# Reference_2V5.net
KiCad netlist of a schematic drawn in Altium Designer
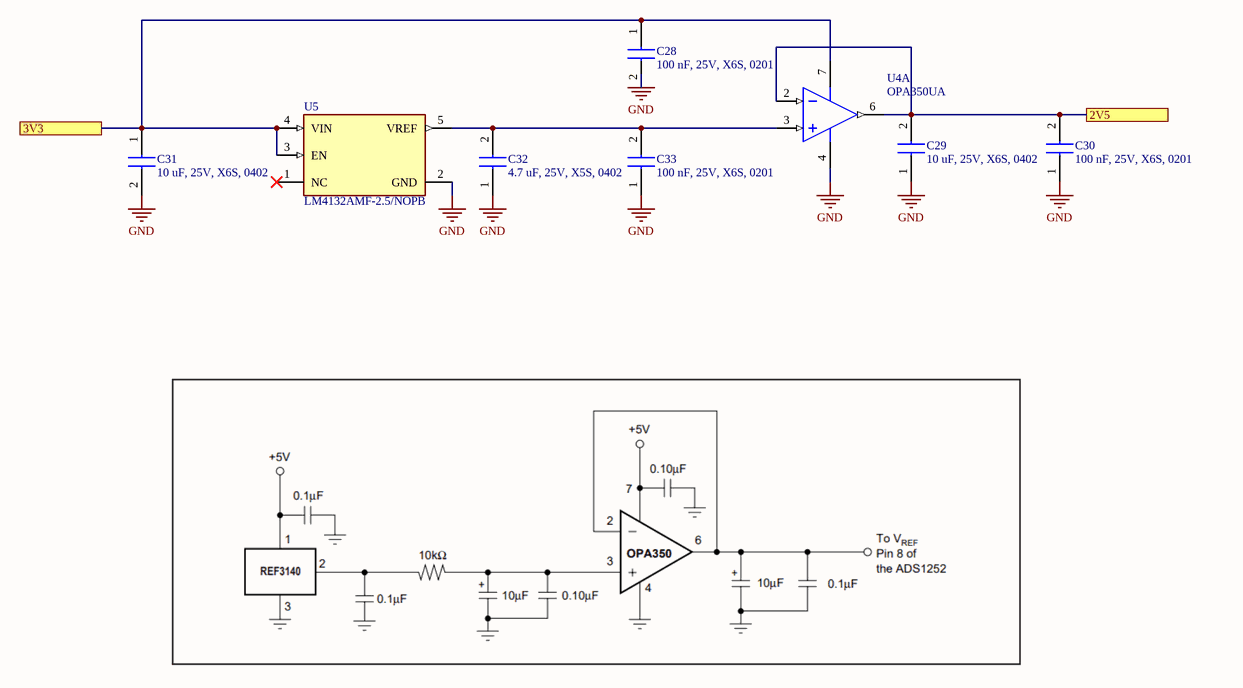
[diagram p0: Reference_2V5.SchDoc]

(export (version "E")
  (design (tool "Eeschema 10.0.6"))
  (components
    (comp (ref "C28")
      (value "100 nF, 25V, X6S, 0201")
      (footprint "SamacSys:CAPC0603X33N")
      (description "Capacitor")
      (fields
        (field (name "MANUFACTURER_PART_NUMBER") "GRM033C81E104KE14D")
        (field (name "MOUSER PART NUMBER") "81-GRM33C81E104KE14D")
      )
      (libsource (lib "*") (part "GRM033C81E104KE14D"))
    )
    (comp (ref "C29")
      (value "10 uF, 25V, X6S, 0402")
      (footprint "SamacSys:CAPC1005X70N")
      (description "Capacitor")
      (fields
        (field (name "MANUFACTURER_PART_NUMBER") "GRM155F51E104ZA01E")
        (field (name "MOUSER PART NUMBER") "81-GRM15F51E104ZA01E")
      )
      (libsource (lib "*") (part "GRM155F51E104ZA01E"))
    )
    (comp (ref "C30")
      (value "100 nF, 25V, X6S, 0201")
      (footprint "SamacSys:CAPC0603X33N")
      (description "Capacitor")
      (fields
        (field (name "MANUFACTURER_PART_NUMBER") "GRM033C81E104KE14D")
        (field (name "MOUSER PART NUMBER") "81-GRM33C81E104KE14D")
      )
      (libsource (lib "*") (part "GRM033C81E104KE14D"))
    )
    (comp (ref "C31")
      (value "10 uF, 25V, X6S, 0402")
      (footprint "SamacSys:CAPC1005X70N")
      (description "Capacitor")
      (fields
        (field (name "MANUFACTURER_PART_NUMBER") "GRM155F51E104ZA01E")
        (field (name "MOUSER PART NUMBER") "81-GRM15F51E104ZA01E")
      )
      (libsource (lib "*") (part "GRM155F51E104ZA01E"))
    )
    (comp (ref "C32")
      (value "4.7 uF, 25V, X5S, 0402")
      (footprint "SamacSys:GRM15x")
      (description "Capacitor")
      (fields
        (field (name "MANUFACTURER_PART_NUMBER") "GRM155C61E475ME15J")
        (field (name "MOUSER PART NUMBER") "81-GRM15C61E475ME15J")
      )
      (libsource (lib "*") (part "GRM155C61E475ME15J"))
    )
    (comp (ref "C33")
      (value "100 nF, 25V, X6S, 0201")
      (footprint "SamacSys:CAPC0603X33N")
      (description "Capacitor")
      (fields
        (field (name "MANUFACTURER_PART_NUMBER") "GRM033C81E104KE14D")
        (field (name "MOUSER PART NUMBER") "81-GRM33C81E104KE14D")
      )
      (libsource (lib "*") (part "GRM033C81E104KE14D"))
    )
    (comp (ref "U4")
      (value "OPA350UA")
      (footprint "D0008A_M")
      (fields (field (name "MANUFACTURER") "Texas Instruments"))
      (libsource (lib "Altium Content Vault") (part "TI-OPA-8_1"))
    )
    (comp (ref "U5")
      (value "LM4132AMF-2.5/NOPB")
      (footprint "FP-DBV0005A-IPC_C")
      (description "IC VREF SERIES 0.05% SOT23-5")
      (fields (field (name "TOLERANCE") "0.05%"))
      (libsource (lib "Altium Content Vault") (part "83a8c20666b8818ecf60699c622df6d"))
    )
  )
  (nets
    (net (code "1") (name "/2V5") (class "Default")
      (node (ref "C29") (pin "2") (pinfunction "2_2") (pintype "passive"))
      (node (ref "C30") (pin "2") (pinfunction "2_2") (pintype "passive"))
      (node (ref "U4") (pin "2") (pinfunction "IN-_2") (pintype "input"))
      (node (ref "U4") (pin "6") (pinfunction "OUT_6") (pintype "output"))
    )
    (net (code "2") (name "/3V3") (class "Default")
      (node (ref "C28") (pin "1") (pinfunction "1_1") (pintype "passive"))
      (node (ref "C31") (pin "1") (pinfunction "1_1") (pintype "passive"))
      (node (ref "U4") (pin "7") (pinfunction "V+_7") (pintype "power_in"))
      (node (ref "U5") (pin "3") (pinfunction "EN_3") (pintype "input"))
      (node (ref "U5") (pin "4") (pinfunction "VIN_4") (pintype "input"))
    )
    (net (code "3") (name "GND") (class "Default")
      (node (ref "C28") (pin "2") (pinfunction "2_2") (pintype "passive"))
      (node (ref "C29") (pin "1") (pinfunction "1_1") (pintype "passive"))
      (node (ref "C30") (pin "1") (pinfunction "1_1") (pintype "passive"))
      (node (ref "C31") (pin "2") (pinfunction "2_2") (pintype "passive"))
      (node (ref "C32") (pin "1") (pinfunction "1_1") (pintype "passive"))
      (node (ref "C33") (pin "1") (pinfunction "1_1") (pintype "passive"))
      (node (ref "U4") (pin "4") (pinfunction "V-_4") (pintype "power_in"))
      (node (ref "U5") (pin "2") (pinfunction "GND_2") (pintype "power_in"))
    )
    (net (code "4") (name "Net-(U4A-IN+)") (class "Default")
      (node (ref "C32") (pin "2") (pinfunction "2_2") (pintype "passive"))
      (node (ref "C33") (pin "2") (pinfunction "2_2") (pintype "passive"))
      (node (ref "U4") (pin "3") (pinfunction "IN+_3") (pintype "input"))
      (node (ref "U5") (pin "5") (pinfunction "VREF_5") (pintype "output"))
    )
    (net (code "5") (name "unconnected-(U5-NC-Pad1)") (class "Default")
      (node (ref "U5") (pin "1") (pinfunction "NC_1") (pintype "passive+no_connect"))
    )
  )
)
